# esquematico.net
KiCad netlist of a schematic drawn in Altium Designer
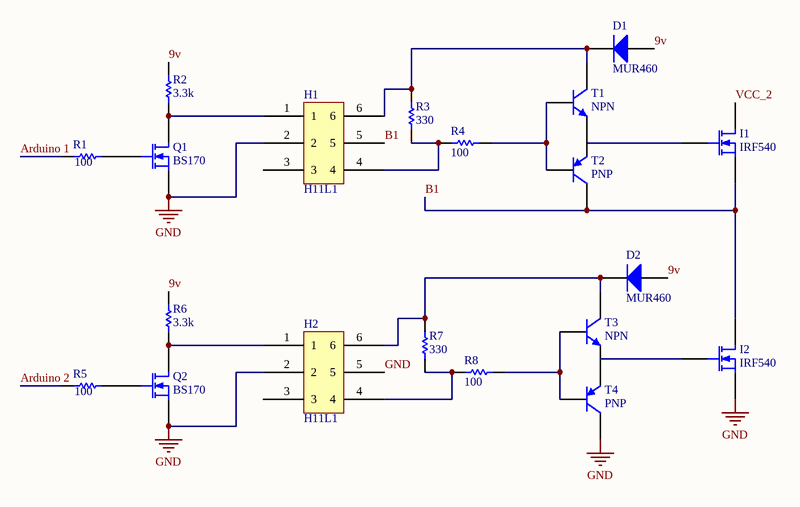
[diagram p0: esquematico.SchDoc]

(export (version "E")
  (design (tool "Eeschema 10.0.6"))
  (components
    (comp (ref "D1")
      (value "MUR460")
      (footprint "DO201T15")
      (description "Default Diode")
      (fields (field (name "PUBLISHER") "Altium Limited"))
      (libsource (lib "Miscellaneous Devices") (part "Diode"))
    )
    (comp (ref "D2")
      (value "MUR460")
      (footprint "DO201T15")
      (description "Default Diode")
      (fields (field (name "PUBLISHER") "Altium Limited"))
      (libsource (lib "Miscellaneous Devices") (part "Diode"))
    )
    (comp (ref "H1") (value "H11L1") (footprint "DIP-6") (libsource (lib "H11L1") (part "H11L1")))
    (comp (ref "H2") (value "H11L1") (footprint "DIP-6") (libsource (lib "H11L1") (part "H11L1")))
    (comp (ref "I1")
      (value "IRF540")
      (footprint "TO-220AB")
      (description "N-Channel MOSFET")
      (fields (field (name "PUBLISHER") "Altium Limited"))
      (libsource (lib "Miscellaneous Devices") (part "MOSFET-N"))
    )
    (comp (ref "I2")
      (value "IRF540")
      (footprint "TO-220-AB")
      (description "N-Channel MOSFET")
      (fields (field (name "PUBLISHER") "Altium Limited"))
      (libsource (lib "Miscellaneous Devices") (part "MOSFET-N"))
    )
    (comp (ref "Q1")
      (value "BS170")
      (footprint "E3")
      (description "N-Channel MOSFET")
      (fields (field (name "PUBLISHER") "Altium Limited"))
      (libsource (lib "Miscellaneous Devices") (part "MOSFET-N"))
    )
    (comp (ref "Q2")
      (value "BS170")
      (footprint "E3")
      (description "N-Channel MOSFET")
      (fields (field (name "PUBLISHER") "Altium Limited"))
      (libsource (lib "Miscellaneous Devices") (part "MOSFET-N"))
    )
    (comp (ref "R1")
      (value "100")
      (footprint "3216[1206]")
      (description "Resistor")
      (fields (field (name "Comment") "Res1") (field (name "PUBLISHER") "Altium Limited"))
      (libsource (lib "Miscellaneous Devices") (part "Res1"))
    )
    (comp (ref "R2")
      (value "3.3k")
      (footprint "3216[1206]")
      (description "Resistor")
      (fields (field (name "Comment") "Res1") (field (name "PUBLISHER") "Altium Limited"))
      (libsource (lib "Miscellaneous Devices") (part "Res1"))
    )
    (comp (ref "R3")
      (value "330")
      (footprint "3216[1206]")
      (description "Resistor")
      (fields (field (name "Comment") "Res1") (field (name "PUBLISHER") "Altium Limited"))
      (libsource (lib "Miscellaneous Devices") (part "Res1"))
    )
    (comp (ref "R4")
      (value "100")
      (footprint "3216[1206]")
      (description "Resistor")
      (fields (field (name "Comment") "Res1") (field (name "PUBLISHER") "Altium Limited"))
      (libsource (lib "Miscellaneous Devices") (part "Res1"))
    )
    (comp (ref "R5")
      (value "100")
      (footprint "3216[1206]")
      (description "Resistor")
      (fields (field (name "Comment") "Res1") (field (name "PUBLISHER") "Altium Limited"))
      (libsource (lib "Miscellaneous Devices") (part "Res1"))
    )
    (comp (ref "R6")
      (value "3.3k")
      (footprint "3216[1206]")
      (description "Resistor")
      (fields (field (name "Comment") "Res1") (field (name "PUBLISHER") "Altium Limited"))
      (libsource (lib "Miscellaneous Devices") (part "Res1"))
    )
    (comp (ref "R7")
      (value "330")
      (footprint "3216[1206]")
      (description "Resistor")
      (fields (field (name "Comment") "Res1") (field (name "PUBLISHER") "Altium Limited"))
      (libsource (lib "Miscellaneous Devices") (part "Res1"))
    )
    (comp (ref "R8")
      (value "100")
      (footprint "3216[1206]")
      (description "Resistor")
      (fields (field (name "Comment") "Res1") (field (name "PUBLISHER") "Altium Limited"))
      (libsource (lib "Miscellaneous Devices") (part "Res1"))
    )
    (comp (ref "T1")
      (value "NPN")
      (footprint "TO-220-AB")
      (description "NPN Bipolar Transistor")
      (fields (field (name "PUBLISHER") "Altium Limited"))
      (libsource (lib "Miscellaneous Devices") (part "NPN"))
    )
    (comp (ref "T2")
      (value "PNP")
      (footprint "TO-220-AB")
      (description "PNP Bipolar Transistor")
      (fields (field (name "PUBLISHER") "Altium Limited"))
      (libsource (lib "Miscellaneous Devices") (part "PNP"))
    )
    (comp (ref "T3")
      (value "NPN")
      (footprint "TO-220-AB")
      (description "NPN Bipolar Transistor")
      (fields (field (name "PUBLISHER") "Altium Limited"))
      (libsource (lib "Miscellaneous Devices") (part "NPN"))
    )
    (comp (ref "T4")
      (value "PNP")
      (footprint "TO-220-AB")
      (description "PNP Bipolar Transistor")
      (fields (field (name "PUBLISHER") "Altium Limited"))
      (libsource (lib "Miscellaneous Devices") (part "PNP"))
    )
  )
  (nets
    (net (code "1") (name "/9v") (class "Default")
      (node (ref "D1") (pin "1") (pinfunction "A_1") (pintype "passive"))
      (node (ref "D2") (pin "1") (pinfunction "A_1") (pintype "passive"))
      (node (ref "R2") (pin "2") (pinfunction "2_2") (pintype "passive"))
      (node (ref "R6") (pin "2") (pinfunction "2_2") (pintype "passive"))
    )
    (net (code "2") (name "/Arduino 1") (class "Default")
      (node (ref "R1") (pin "1") (pinfunction "1_1") (pintype "passive"))
    )
    (net (code "3") (name "/Arduino 2") (class "Default")
      (node (ref "R5") (pin "1") (pinfunction "1_1") (pintype "passive"))
    )
    (net (code "4") (name "/B1") (class "Default")
      (node (ref "H1") (pin "5") (pinfunction "5_5") (pintype "passive"))
      (node (ref "I1") (pin "3") (pinfunction "S_3") (pintype "passive"))
      (node (ref "I2") (pin "1") (pinfunction "D_1") (pintype "passive"))
      (node (ref "T2") (pin "1") (pinfunction "C_1") (pintype "passive"))
    )
    (net (code "5") (name "/VCC_2") (class "Default")
      (node (ref "I1") (pin "1") (pinfunction "D_1") (pintype "passive"))
    )
    (net (code "6") (name "GND") (class "Default")
      (node (ref "H1") (pin "2") (pinfunction "2_2") (pintype "passive"))
      (node (ref "H2") (pin "2") (pinfunction "2_2") (pintype "passive"))
      (node (ref "H2") (pin "5") (pinfunction "5_5") (pintype "passive"))
      (node (ref "I2") (pin "3") (pinfunction "S_3") (pintype "passive"))
      (node (ref "Q1") (pin "3") (pinfunction "S_3") (pintype "passive"))
      (node (ref "Q2") (pin "3") (pinfunction "S_3") (pintype "passive"))
      (node (ref "T4") (pin "1") (pinfunction "C_1") (pintype "passive"))
    )
    (net (code "7") (name "Net-(D1-K)") (class "Default")
      (node (ref "D1") (pin "2") (pinfunction "K_2") (pintype "passive"))
      (node (ref "H1") (pin "6") (pinfunction "6_6") (pintype "passive"))
      (node (ref "R3") (pin "2") (pinfunction "2_2") (pintype "passive"))
      (node (ref "T1") (pin "1") (pinfunction "C_1") (pintype "passive"))
    )
    (net (code "8") (name "Net-(D2-K)") (class "Default")
      (node (ref "D2") (pin "2") (pinfunction "K_2") (pintype "passive"))
      (node (ref "H2") (pin "6") (pinfunction "6_6") (pintype "passive"))
      (node (ref "R7") (pin "2") (pinfunction "2_2") (pintype "passive"))
      (node (ref "T3") (pin "1") (pinfunction "C_1") (pintype "passive"))
    )
    (net (code "9") (name "Net-(H1-Pad4)") (class "Default")
      (node (ref "H1") (pin "4") (pinfunction "4_4") (pintype "passive"))
      (node (ref "R3") (pin "1") (pinfunction "1_1") (pintype "passive"))
      (node (ref "R4") (pin "2") (pinfunction "2_2") (pintype "passive"))
    )
    (net (code "10") (name "Net-(H2-Pad4)") (class "Default")
      (node (ref "H2") (pin "4") (pinfunction "4_4") (pintype "passive"))
      (node (ref "R7") (pin "1") (pinfunction "1_1") (pintype "passive"))
      (node (ref "R8") (pin "2") (pinfunction "2_2") (pintype "passive"))
    )
    (net (code "11") (name "Net-(I1-G)") (class "Default")
      (node (ref "I1") (pin "2") (pinfunction "G_2") (pintype "passive"))
      (node (ref "T1") (pin "3") (pinfunction "E_3") (pintype "passive"))
    )
    (net (code "12") (name "Net-(I2-G)") (class "Default")
      (node (ref "I2") (pin "2") (pinfunction "G_2") (pintype "passive"))
      (node (ref "T4") (pin "3") (pinfunction "E_3") (pintype "passive"))
    )
    (net (code "13") (name "Net-(Q1-D)") (class "Default")
      (node (ref "H1") (pin "1") (pinfunction "1_1") (pintype "passive"))
      (node (ref "Q1") (pin "1") (pinfunction "D_1") (pintype "passive"))
      (node (ref "R2") (pin "1") (pinfunction "1_1") (pintype "passive"))
    )
    (net (code "14") (name "Net-(Q1-G)") (class "Default")
      (node (ref "Q1") (pin "2") (pinfunction "G_2") (pintype "passive"))
      (node (ref "R1") (pin "2") (pinfunction "2_2") (pintype "passive"))
    )
    (net (code "15") (name "Net-(Q2-D)") (class "Default")
      (node (ref "H2") (pin "1") (pinfunction "1_1") (pintype "passive"))
      (node (ref "Q2") (pin "1") (pinfunction "D_1") (pintype "passive"))
      (node (ref "R6") (pin "1") (pinfunction "1_1") (pintype "passive"))
    )
    (net (code "16") (name "Net-(Q2-G)") (class "Default")
      (node (ref "Q2") (pin "2") (pinfunction "G_2") (pintype "passive"))
      (node (ref "R5") (pin "2") (pinfunction "2_2") (pintype "passive"))
    )
    (net (code "17") (name "Net-(T1-B)") (class "Default")
      (node (ref "R4") (pin "1") (pinfunction "1_1") (pintype "passive"))
      (node (ref "T1") (pin "2") (pinfunction "B_2") (pintype "passive"))
      (node (ref "T2") (pin "2") (pinfunction "B_2") (pintype "passive"))
    )
    (net (code "18") (name "Net-(T3-B)") (class "Default")
      (node (ref "R8") (pin "1") (pinfunction "1_1") (pintype "passive"))
      (node (ref "T3") (pin "2") (pinfunction "B_2") (pintype "passive"))
      (node (ref "T4") (pin "2") (pinfunction "B_2") (pintype "passive"))
    )
    (net (code "19") (name "unconnected-(H1-Pad3)") (class "Default")
      (node (ref "H1") (pin "3") (pinfunction "3_3") (pintype "passive"))
    )
    (net (code "20") (name "unconnected-(H2-Pad3)") (class "Default")
      (node (ref "H2") (pin "3") (pinfunction "3_3") (pintype "passive"))
    )
    (net (code "21") (name "unconnected-(T2-E-Pad3)") (class "Default")
      (node (ref "T2") (pin "3") (pinfunction "E_3") (pintype "passive"))
    )
    (net (code "22") (name "unconnected-(T3-E-Pad3)") (class "Default")
      (node (ref "T3") (pin "3") (pinfunction "E_3") (pintype "passive"))
    )
  )
)
